# teensy-jst_01_4_v6.net
KiCad netlist of a schematic drawn in EAGLE
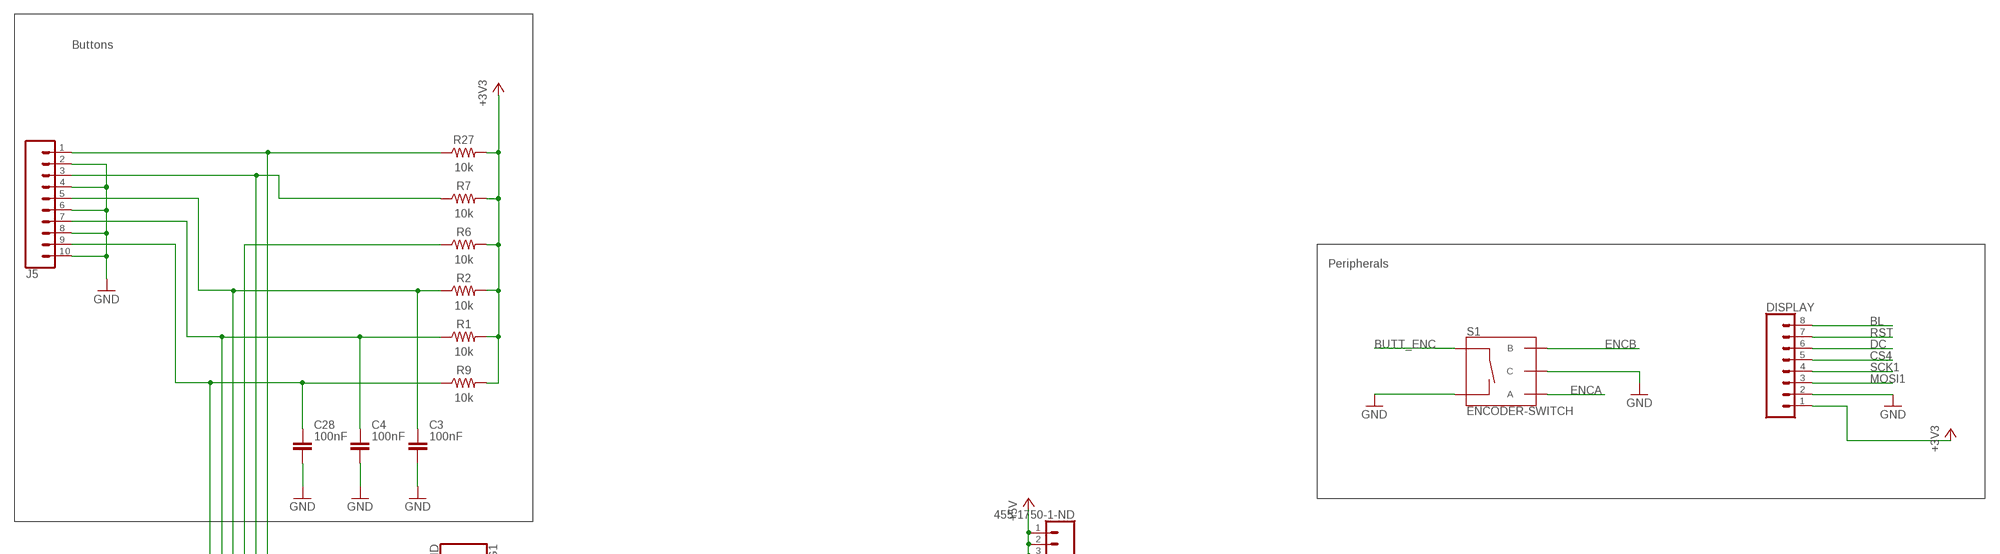
[diagram p0: schematic, sheet 1, part 1 of 3]
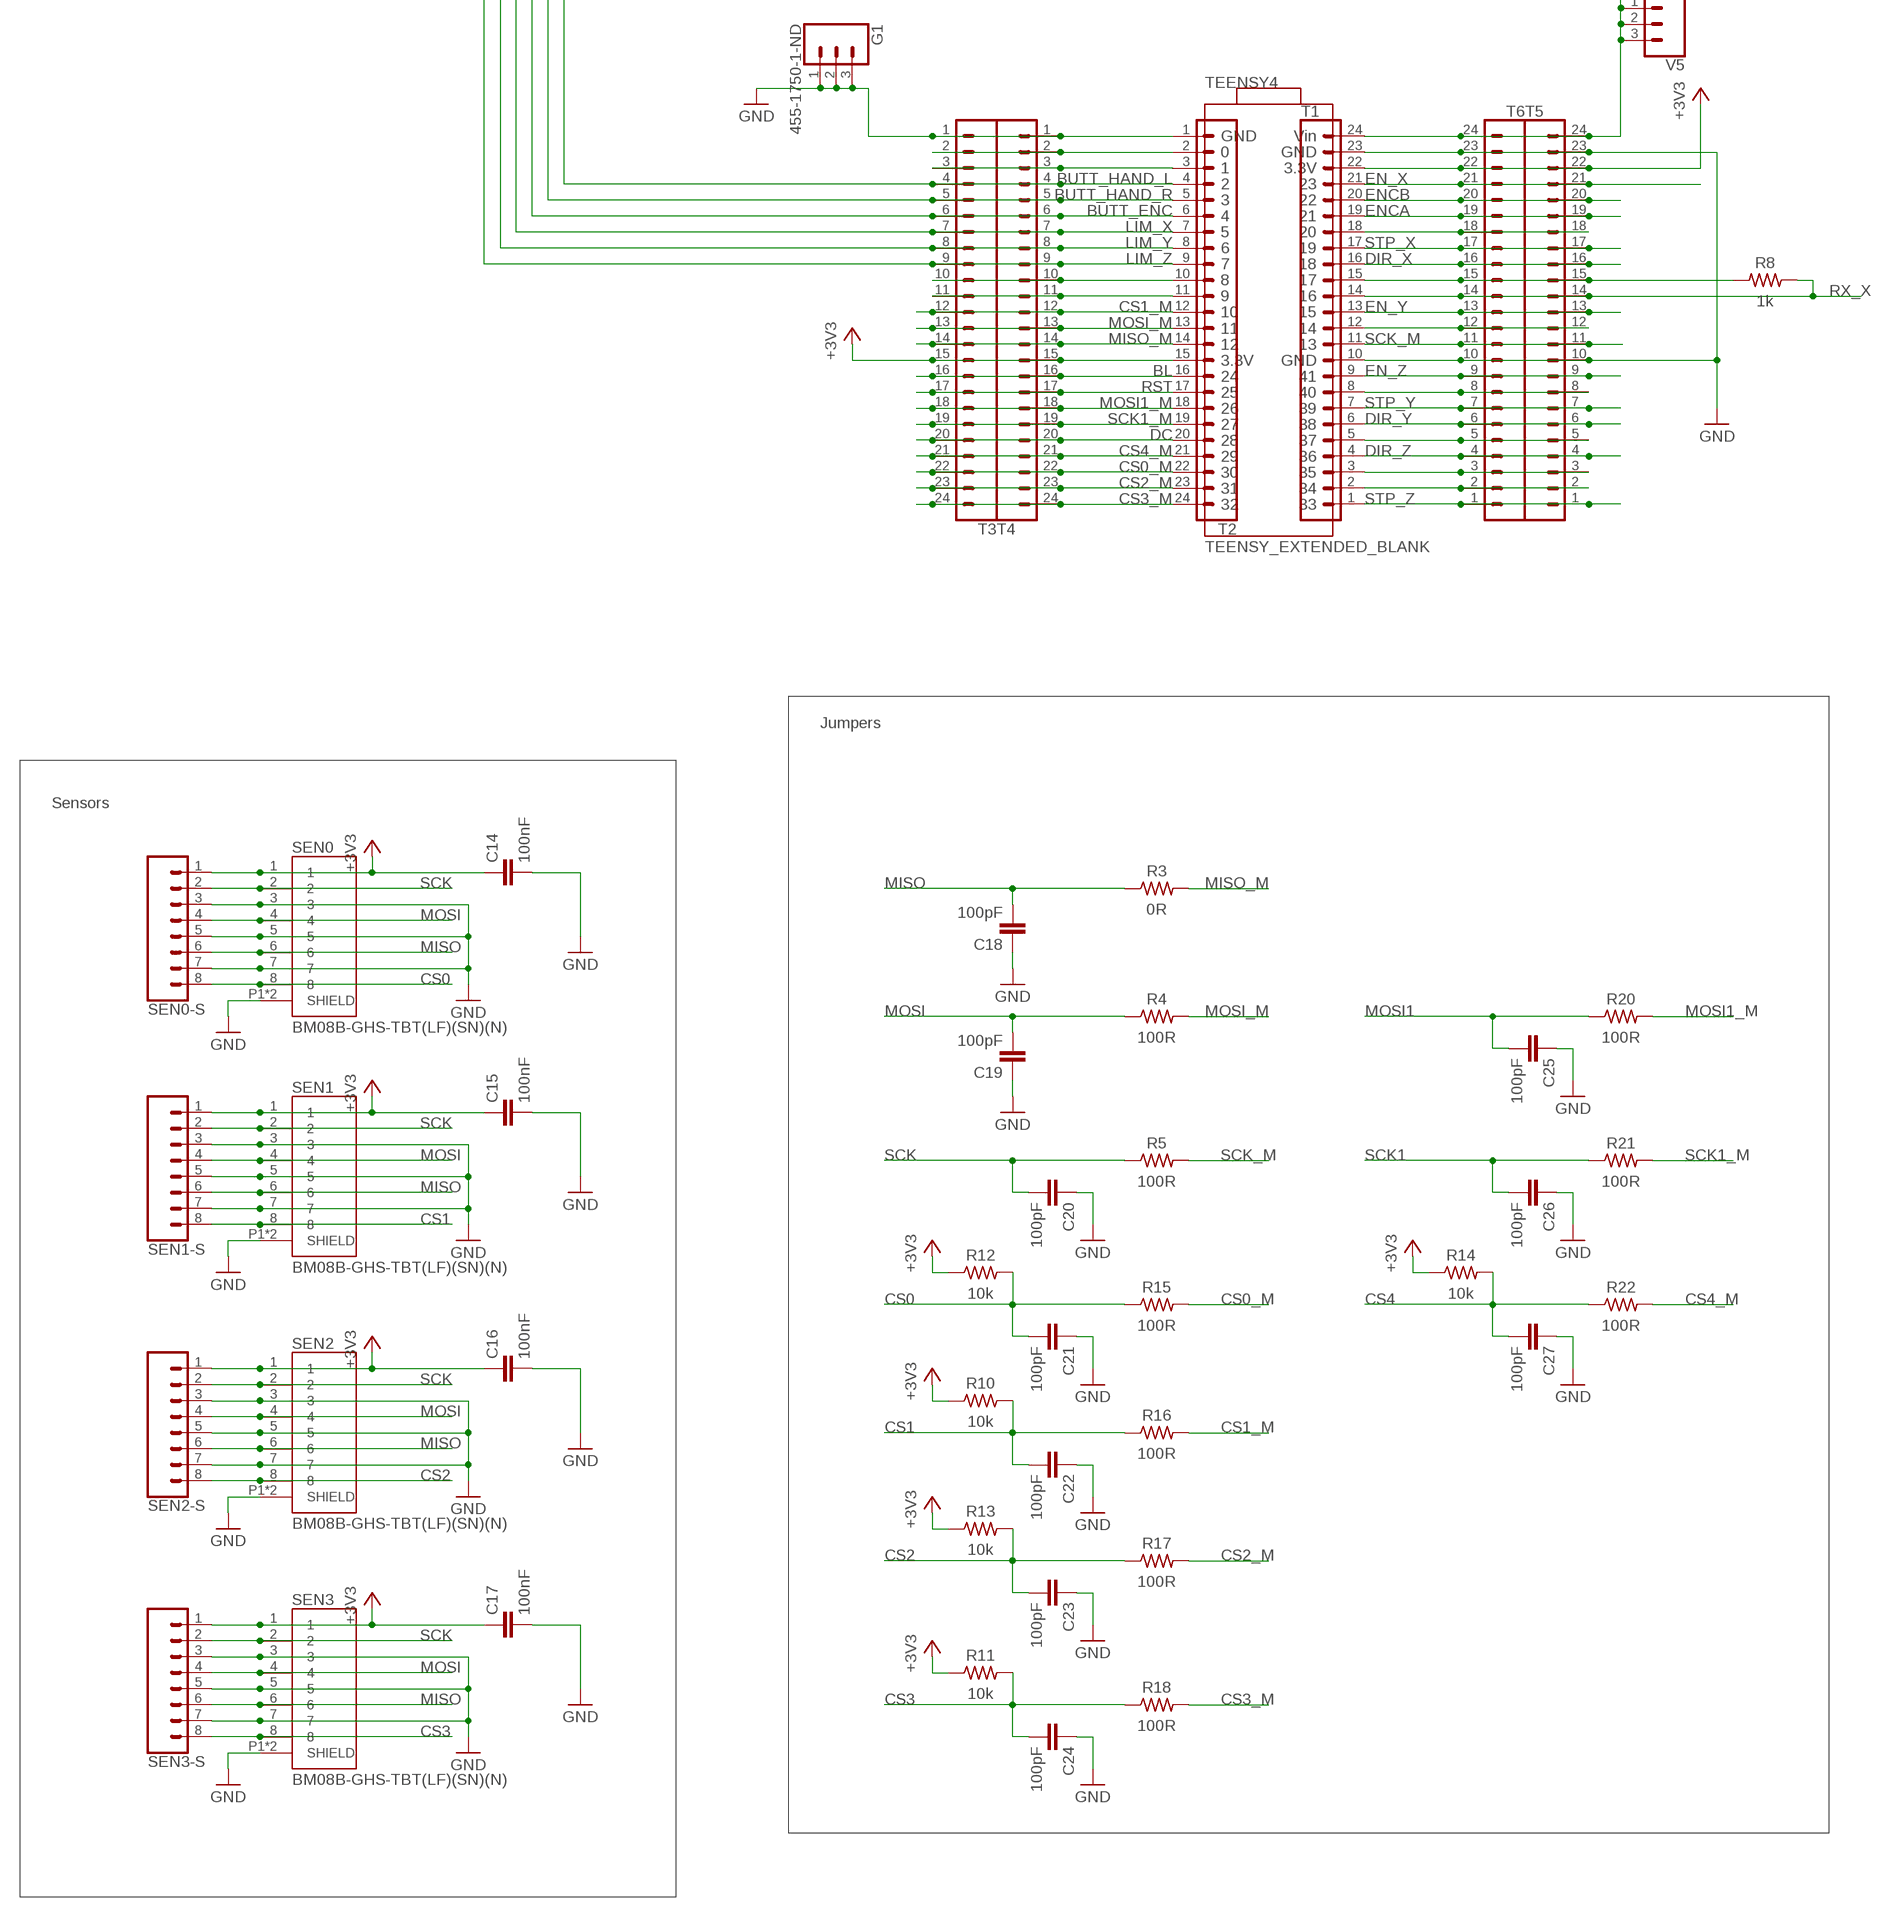
[diagram p1: schematic, sheet 1, part 2 of 3]
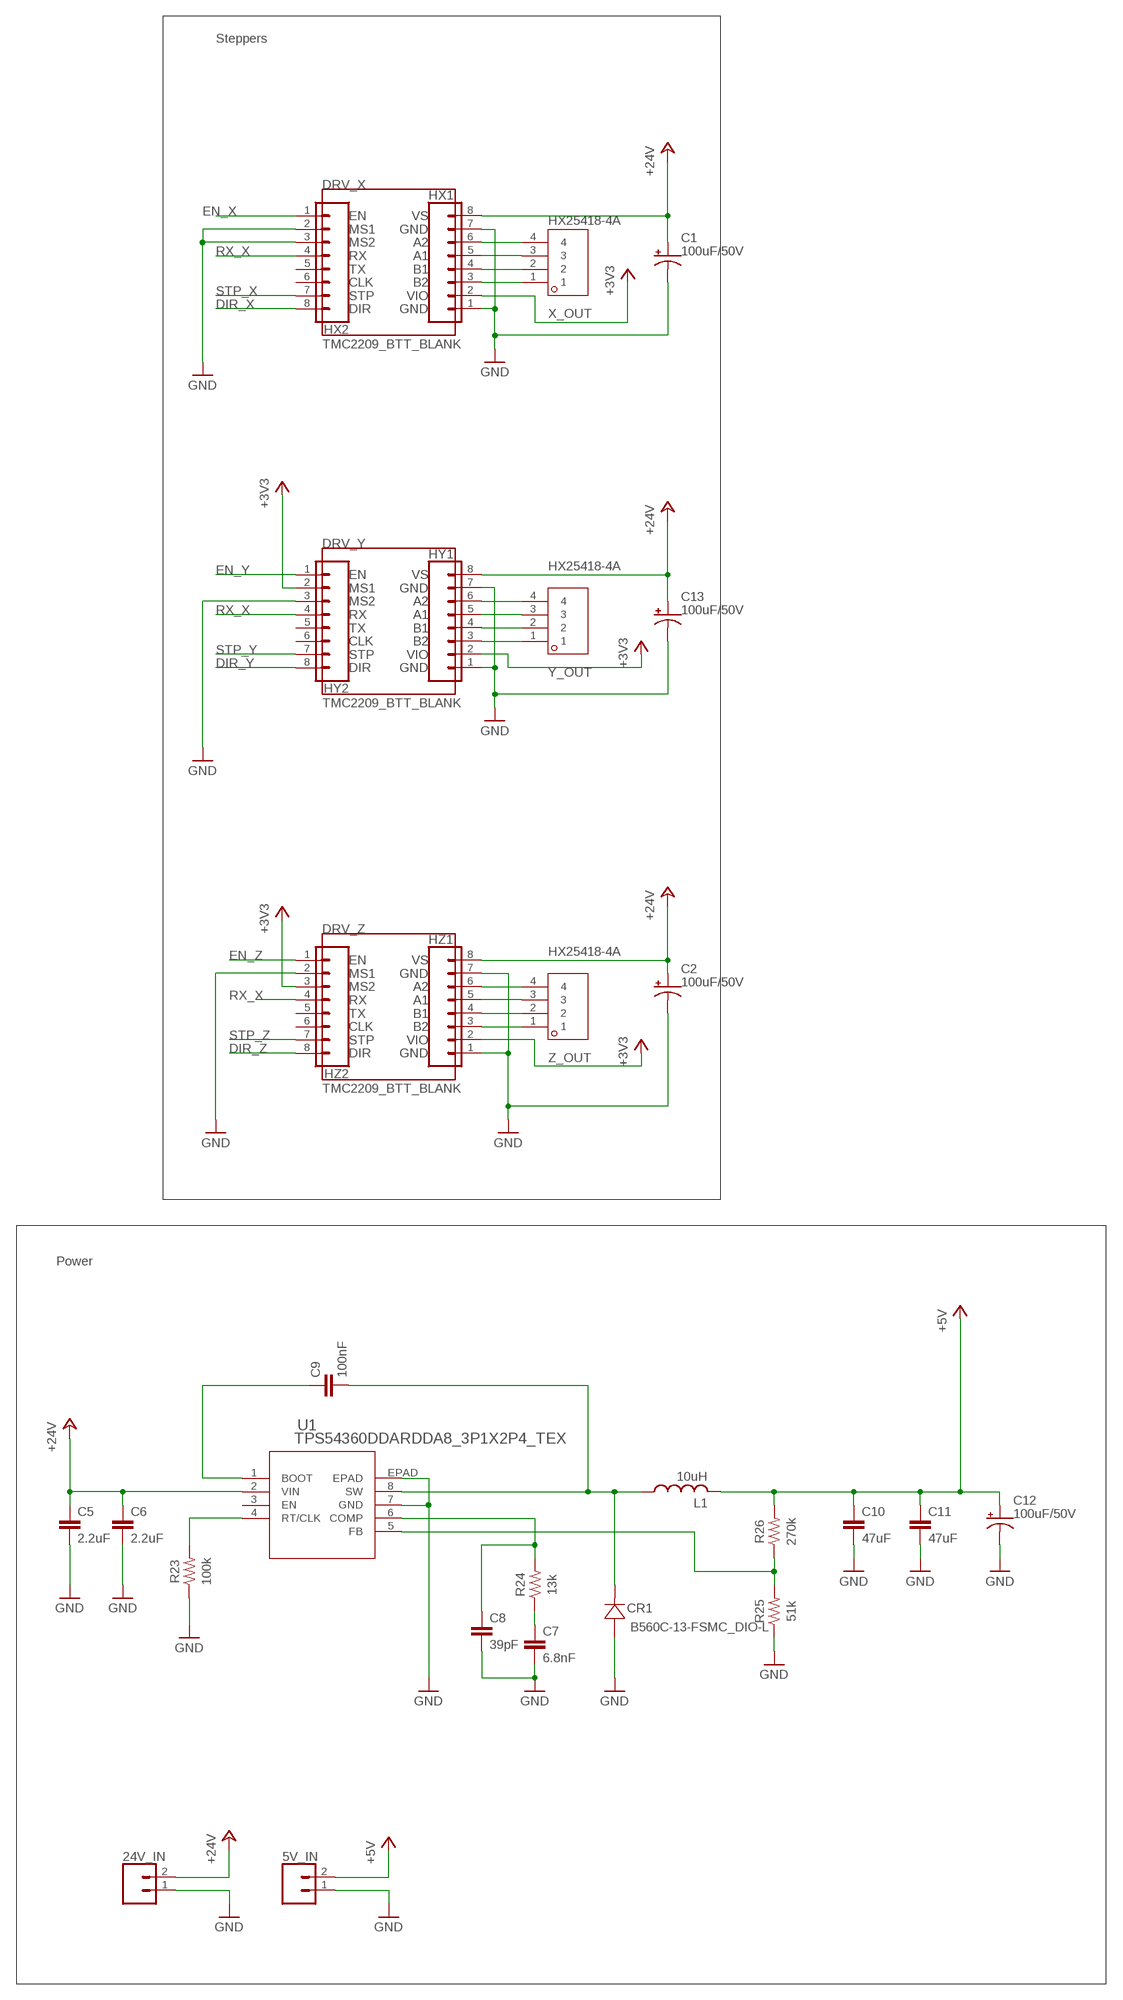
[diagram p2: schematic, sheet 1, part 3 of 3]

(export (version "E")
  (design (tool "Eeschema 10.0.6"))
  (components
    (comp (ref "5V_IN")
      (value "CONN_025MM")
      (footprint "eagle-import:SCREWTERMINAL-5MM-2")
      (libsource (lib "eagle-import") (part "CONN_025MM"))
    )
    (comp (ref "24V_IN")
      (value "CONN_025MM")
      (footprint "eagle-import:SCREWTERMINAL-5MM-2")
      (libsource (lib "eagle-import") (part "CONN_025MM"))
    )
    (comp (ref "C1")
      (value "100uF/50V")
      (footprint "eagle-import:PANASONIC_D")
      (libsource (lib "eagle-import") (part "CPOL-USD"))
    )
    (comp (ref "C2")
      (value "100uF/50V")
      (footprint "eagle-import:PANASONIC_D")
      (libsource (lib "eagle-import") (part "CPOL-USD"))
    )
    (comp (ref "C3")
      (value "100nF")
      (footprint "eagle-import:CAPC1608X85")
      (libsource (lib "eagle-import") (part "CCHIP-0603(1608-METRIC)_"))
    )
    (comp (ref "C4")
      (value "100nF")
      (footprint "eagle-import:CAPC1608X85")
      (libsource (lib "eagle-import") (part "CCHIP-0603(1608-METRIC)_"))
    )
    (comp (ref "C5")
      (value "2.2uF")
      (footprint "eagle-import:CAPC1608X85")
      (libsource (lib "eagle-import") (part "CCHIP-0603(1608-METRIC)_"))
    )
    (comp (ref "C6")
      (value "2.2uF")
      (footprint "eagle-import:CAPC1608X85")
      (libsource (lib "eagle-import") (part "CCHIP-0603(1608-METRIC)_"))
    )
    (comp (ref "C7")
      (value "6.8nF")
      (footprint "eagle-import:CAPC1608X85")
      (libsource (lib "eagle-import") (part "CCHIP-0603(1608-METRIC)_"))
    )
    (comp (ref "C8")
      (value "39pF")
      (footprint "eagle-import:CAPC1005X60")
      (libsource (lib "eagle-import") (part "CCHIP-0402(1005-METRIC)_"))
    )
    (comp (ref "C9")
      (value "100nF")
      (footprint "eagle-import:CAPC1005X60")
      (libsource (lib "eagle-import") (part "CCHIP-0402(1005-METRIC)_"))
    )
    (comp (ref "C10")
      (value "47uF")
      (footprint "eagle-import:CAPC2012X110")
      (libsource (lib "eagle-import") (part "CCHIP-0805(2012-METRIC)_"))
    )
    (comp (ref "C11")
      (value "47uF")
      (footprint "eagle-import:CAPC2012X110")
      (libsource (lib "eagle-import") (part "CCHIP-0805(2012-METRIC)_"))
    )
    (comp (ref "C12")
      (value "100uF/50V")
      (footprint "eagle-import:PANASONIC_D")
      (libsource (lib "eagle-import") (part "CPOL-USD"))
    )
    (comp (ref "C13")
      (value "100uF/50V")
      (footprint "eagle-import:PANASONIC_D")
      (libsource (lib "eagle-import") (part "CPOL-USD"))
    )
    (comp (ref "C14")
      (value "100nF")
      (footprint "eagle-import:CAPC1005X60")
      (libsource (lib "eagle-import") (part "CCHIP-0402(1005-METRIC)_"))
    )
    (comp (ref "C15")
      (value "100nF")
      (footprint "eagle-import:CAPC1005X60")
      (libsource (lib "eagle-import") (part "CCHIP-0402(1005-METRIC)_"))
    )
    (comp (ref "C16")
      (value "100nF")
      (footprint "eagle-import:CAPC1005X60")
      (libsource (lib "eagle-import") (part "CCHIP-0402(1005-METRIC)_"))
    )
    (comp (ref "C17")
      (value "100nF")
      (footprint "eagle-import:CAPC1005X60")
      (libsource (lib "eagle-import") (part "CCHIP-0402(1005-METRIC)_"))
    )
    (comp (ref "C18")
      (value "100pF")
      (footprint "eagle-import:CAPC1005X60")
      (libsource (lib "eagle-import") (part "CCHIP-0402(1005-METRIC)_"))
    )
    (comp (ref "C19")
      (value "100pF")
      (footprint "eagle-import:CAPC1005X60")
      (libsource (lib "eagle-import") (part "CCHIP-0402(1005-METRIC)_"))
    )
    (comp (ref "C20")
      (value "100pF")
      (footprint "eagle-import:CAPC1005X60")
      (libsource (lib "eagle-import") (part "CCHIP-0402(1005-METRIC)_"))
    )
    (comp (ref "C21")
      (value "100pF")
      (footprint "eagle-import:CAPC1005X60")
      (libsource (lib "eagle-import") (part "CCHIP-0402(1005-METRIC)_"))
    )
    (comp (ref "C22")
      (value "100pF")
      (footprint "eagle-import:CAPC1005X60")
      (libsource (lib "eagle-import") (part "CCHIP-0402(1005-METRIC)_"))
    )
    (comp (ref "C23")
      (value "100pF")
      (footprint "eagle-import:CAPC1005X60")
      (libsource (lib "eagle-import") (part "CCHIP-0402(1005-METRIC)_"))
    )
    (comp (ref "C24")
      (value "100pF")
      (footprint "eagle-import:CAPC1005X60")
      (libsource (lib "eagle-import") (part "CCHIP-0402(1005-METRIC)_"))
    )
    (comp (ref "C25")
      (value "100pF")
      (footprint "eagle-import:CAPC1005X60")
      (libsource (lib "eagle-import") (part "CCHIP-0402(1005-METRIC)_"))
    )
    (comp (ref "C26")
      (value "100pF")
      (footprint "eagle-import:CAPC1005X60")
      (libsource (lib "eagle-import") (part "CCHIP-0402(1005-METRIC)_"))
    )
    (comp (ref "C27")
      (value "100pF")
      (footprint "eagle-import:CAPC1005X60")
      (libsource (lib "eagle-import") (part "CCHIP-0402(1005-METRIC)_"))
    )
    (comp (ref "C28")
      (value "100nF")
      (footprint "eagle-import:CAPC1608X85")
      (libsource (lib "eagle-import") (part "CCHIP-0603(1608-METRIC)_"))
    )
    (comp (ref "CR1")
      (value "B560C-13-FSMC_DIO-L")
      (footprint "eagle-import:SMC_DIO-L")
      (fields
        (field (name "MANUFACTURER_PART_NUMBER") "B560C-13-F")
        (field (name "COPYRIGHT") "Copyright (C) 2024 Ultra Librarian. All rights reserved.")
      )
      (libsource (lib "eagle-import") (part "B560C-13-FSMC_DIO-L"))
    )
    (comp (ref "DISPLAY")
      (value "CONN_08\"")
      (footprint "eagle-import:1X08")
      (libsource (lib "eagle-import") (part "CONN_08{dblquote}"))
    )
    (comp (ref "DRV_X")
      (value "TMC2209_BTT_BLANK")
      (footprint "eagle-import:MODULE_TMC2209_BTT_BLANK")
      (libsource (lib "eagle-import") (part "TMC2209_BTT_BLANK"))
    )
    (comp (ref "DRV_Y")
      (value "TMC2209_BTT_BLANK")
      (footprint "eagle-import:MODULE_TMC2209_BTT_BLANK")
      (libsource (lib "eagle-import") (part "TMC2209_BTT_BLANK"))
    )
    (comp (ref "DRV_Z")
      (value "TMC2209_BTT_BLANK")
      (footprint "eagle-import:MODULE_TMC2209_BTT_BLANK")
      (libsource (lib "eagle-import") (part "TMC2209_BTT_BLANK"))
    )
    (comp (ref "G1")
      (value "455-1750-1-ND")
      (footprint "eagle-import:1X03")
      (libsource (lib "eagle-import") (part "CONN_03"))
    )
    (comp (ref "HX1")
      (value "CONN_08\"")
      (footprint "eagle-import:1X08")
      (libsource (lib "eagle-import") (part "CONN_08{dblquote}"))
    )
    (comp (ref "HX2")
      (value "CONN_08\"")
      (footprint "eagle-import:1X08")
      (libsource (lib "eagle-import") (part "CONN_08{dblquote}"))
    )
    (comp (ref "HY1")
      (value "CONN_08\"")
      (footprint "eagle-import:1X08")
      (libsource (lib "eagle-import") (part "CONN_08{dblquote}"))
    )
    (comp (ref "HY2")
      (value "CONN_08\"")
      (footprint "eagle-import:1X08")
      (libsource (lib "eagle-import") (part "CONN_08{dblquote}"))
    )
    (comp (ref "HZ1")
      (value "CONN_08\"")
      (footprint "eagle-import:1X08")
      (libsource (lib "eagle-import") (part "CONN_08{dblquote}"))
    )
    (comp (ref "HZ2")
      (value "CONN_08\"")
      (footprint "eagle-import:1X08")
      (libsource (lib "eagle-import") (part "CONN_08{dblquote}"))
    )
    (comp (ref "J5")
      (value "CONN_10\"")
      (footprint "eagle-import:1X10")
      (libsource (lib "eagle-import") (part "CONN_10{dblquote}"))
    )
    (comp (ref "L1")
      (value "10uH")
      (footprint "eagle-import:MWSA0503S-100MT")
      (libsource (lib "eagle-import") (part "L-USMWSA0503S-100MT"))
    )
    (comp (ref "R1")
      (value "10k")
      (footprint "eagle-import:RESC1608X60")
      (libsource (lib "eagle-import") (part "R-USCHIP-0603(1608-METRIC)_"))
    )
    (comp (ref "R2")
      (value "10k")
      (footprint "eagle-import:RESC1608X60")
      (libsource (lib "eagle-import") (part "R-USCHIP-0603(1608-METRIC)_"))
    )
    (comp (ref "R3")
      (value "0R")
      (footprint "eagle-import:RESC1608X60")
      (libsource (lib "eagle-import") (part "R-USCHIP-0603(1608-METRIC)_"))
    )
    (comp (ref "R4")
      (value "100R")
      (footprint "eagle-import:RESC1608X60")
      (libsource (lib "eagle-import") (part "R-USCHIP-0603(1608-METRIC)_"))
    )
    (comp (ref "R5")
      (value "100R")
      (footprint "eagle-import:RESC1608X60")
      (libsource (lib "eagle-import") (part "R-USCHIP-0603(1608-METRIC)_"))
    )
    (comp (ref "R6")
      (value "10k")
      (footprint "eagle-import:RESC1608X60")
      (libsource (lib "eagle-import") (part "R-USCHIP-0603(1608-METRIC)_"))
    )
    (comp (ref "R7")
      (value "10k")
      (footprint "eagle-import:RESC1608X60")
      (libsource (lib "eagle-import") (part "R-USCHIP-0603(1608-METRIC)_"))
    )
    (comp (ref "R8")
      (value "1k")
      (footprint "eagle-import:RESC1608X60")
      (libsource (lib "eagle-import") (part "R-USCHIP-0603(1608-METRIC)_"))
    )
    (comp (ref "R9")
      (value "10k")
      (footprint "eagle-import:RESC1608X60")
      (libsource (lib "eagle-import") (part "R-USCHIP-0603(1608-METRIC)_"))
    )
    (comp (ref "R10")
      (value "10k")
      (footprint "eagle-import:RESC1608X60")
      (libsource (lib "eagle-import") (part "R-USCHIP-0603(1608-METRIC)_"))
    )
    (comp (ref "R11")
      (value "10k")
      (footprint "eagle-import:RESC1608X60")
      (libsource (lib "eagle-import") (part "R-USCHIP-0603(1608-METRIC)_"))
    )
    (comp (ref "R12")
      (value "10k")
      (footprint "eagle-import:RESC1608X60")
      (libsource (lib "eagle-import") (part "R-USCHIP-0603(1608-METRIC)_"))
    )
    (comp (ref "R13")
      (value "10k")
      (footprint "eagle-import:RESC1608X60")
      (libsource (lib "eagle-import") (part "R-USCHIP-0603(1608-METRIC)_"))
    )
    (comp (ref "R14")
      (value "10k")
      (footprint "eagle-import:RESC1608X60")
      (libsource (lib "eagle-import") (part "R-USCHIP-0603(1608-METRIC)_"))
    )
    (comp (ref "R15")
      (value "100R")
      (footprint "eagle-import:RESC1608X60")
      (libsource (lib "eagle-import") (part "R-USCHIP-0603(1608-METRIC)_"))
    )
    (comp (ref "R16")
      (value "100R")
      (footprint "eagle-import:RESC1608X60")
      (libsource (lib "eagle-import") (part "R-USCHIP-0603(1608-METRIC)_"))
    )
    (comp (ref "R17")
      (value "100R")
      (footprint "eagle-import:RESC1608X60")
      (libsource (lib "eagle-import") (part "R-USCHIP-0603(1608-METRIC)_"))
    )
    (comp (ref "R18")
      (value "100R")
      (footprint "eagle-import:RESC1608X60")
      (libsource (lib "eagle-import") (part "R-USCHIP-0603(1608-METRIC)_"))
    )
    (comp (ref "R20")
      (value "100R")
      (footprint "eagle-import:RESC1608X60")
      (libsource (lib "eagle-import") (part "R-USCHIP-0603(1608-METRIC)_"))
    )
    (comp (ref "R21")
      (value "100R")
      (footprint "eagle-import:RESC1608X60")
      (libsource (lib "eagle-import") (part "R-USCHIP-0603(1608-METRIC)_"))
    )
    (comp (ref "R22")
      (value "100R")
      (footprint "eagle-import:RESC1608X60")
      (libsource (lib "eagle-import") (part "R-USCHIP-0603(1608-METRIC)_"))
    )
    (comp (ref "R23")
      (value "100k")
      (footprint "eagle-import:RESC1005X40")
      (libsource (lib "eagle-import") (part "R-USCHIP-0402(1005-METRIC)_"))
    )
    (comp (ref "R24")
      (value "13k")
      (footprint "eagle-import:RESC1608X60")
      (libsource (lib "eagle-import") (part "R-USCHIP-0603(1608-METRIC)_"))
    )
    (comp (ref "R25")
      (value "51k")
      (footprint "eagle-import:RESC1608X60")
      (libsource (lib "eagle-import") (part "R-USCHIP-0603(1608-METRIC)_"))
    )
    (comp (ref "R26")
      (value "270k")
      (footprint "eagle-import:RESC1005X40")
      (libsource (lib "eagle-import") (part "R-USCHIP-0402(1005-METRIC)_"))
    )
    (comp (ref "R27")
      (value "10k")
      (footprint "eagle-import:RESC1608X60")
      (libsource (lib "eagle-import") (part "R-USCHIP-0603(1608-METRIC)_"))
    )
    (comp (ref "S1")
      (value "ENCODER-SWITCH")
      (footprint "eagle-import:ROTARY_ENC_PLAIN")
      (libsource (lib "eagle-import") (part "ENCODER-SWITCH"))
    )
    (comp (ref "SEN0")
      (value "BM08B-GHS-TBT(LF)(SN)(N)")
      (footprint "eagle-import:JST_BM08B-GHS-TBT(LF)(SN)(N)")
      (fields (field (name "MF") "JST Sales"))
      (libsource (lib "eagle-import") (part "BM08B-GHS-TBT(LF)(SN)(N)"))
    )
    (comp (ref "SEN0-S")
      (value "CONN_08\"")
      (footprint "eagle-import:1X08")
      (libsource (lib "eagle-import") (part "CONN_08{dblquote}"))
    )
    (comp (ref "SEN1")
      (value "BM08B-GHS-TBT(LF)(SN)(N)")
      (footprint "eagle-import:JST_BM08B-GHS-TBT(LF)(SN)(N)")
      (fields (field (name "MF") "JST Sales"))
      (libsource (lib "eagle-import") (part "BM08B-GHS-TBT(LF)(SN)(N)"))
    )
    (comp (ref "SEN1-S")
      (value "CONN_08\"")
      (footprint "eagle-import:1X08")
      (libsource (lib "eagle-import") (part "CONN_08{dblquote}"))
    )
    (comp (ref "SEN2")
      (value "BM08B-GHS-TBT(LF)(SN)(N)")
      (footprint "eagle-import:JST_BM08B-GHS-TBT(LF)(SN)(N)")
      (fields (field (name "MF") "JST Sales"))
      (libsource (lib "eagle-import") (part "BM08B-GHS-TBT(LF)(SN)(N)"))
    )
    (comp (ref "SEN2-S")
      (value "CONN_08\"")
      (footprint "eagle-import:1X08")
      (libsource (lib "eagle-import") (part "CONN_08{dblquote}"))
    )
    (comp (ref "SEN3")
      (value "BM08B-GHS-TBT(LF)(SN)(N)")
      (footprint "eagle-import:JST_BM08B-GHS-TBT(LF)(SN)(N)")
      (fields (field (name "MF") "JST Sales"))
      (libsource (lib "eagle-import") (part "BM08B-GHS-TBT(LF)(SN)(N)"))
    )
    (comp (ref "SEN3-S")
      (value "CONN_08\"")
      (footprint "eagle-import:1X08")
      (libsource (lib "eagle-import") (part "CONN_08{dblquote}"))
    )
    (comp (ref "T1")
      (value "CONN_24")
      (footprint "eagle-import:1X24")
      (libsource (lib "eagle-import") (part "CONN_24"))
    )
    (comp (ref "T2")
      (value "CONN_24")
      (footprint "eagle-import:1X24")
      (libsource (lib "eagle-import") (part "CONN_24"))
    )
    (comp (ref "T3")
      (value "CONN_24")
      (footprint "eagle-import:1X24")
      (libsource (lib "eagle-import") (part "CONN_24"))
    )
    (comp (ref "T4")
      (value "CONN_24")
      (footprint "eagle-import:1X24")
      (libsource (lib "eagle-import") (part "CONN_24"))
    )
    (comp (ref "T5")
      (value "CONN_24")
      (footprint "eagle-import:1X24")
      (libsource (lib "eagle-import") (part "CONN_24"))
    )
    (comp (ref "T6")
      (value "CONN_24")
      (footprint "eagle-import:1X24")
      (libsource (lib "eagle-import") (part "CONN_24"))
    )
    (comp (ref "TEENSY4")
      (value "TEENSY_EXTENDED_BLANK")
      (footprint "eagle-import:TEENSY_EXTENDED_BLANK")
      (libsource (lib "eagle-import") (part "TEENSY_EXTENDED_BLANK"))
    )
    (comp (ref "U1")
      (value "TPS54360DDARDDA8_3P1X2P4_TEX")
      (footprint "eagle-import:DDA8_3P1X2P4_TEX")
      (fields
        (field (name "MANUFACTURER_PART_NUMBER") "TPS54360DDAR")
        (field (name "COPYRIGHT") "Copyright (C) 2024 Ultra Librarian. All rights reserved.")
      )
      (libsource (lib "eagle-import") (part "TPS54360DDARDDA8_3P1X2P4_TEX"))
    )
    (comp (ref "V5")
      (value "455-1750-1-ND")
      (footprint "eagle-import:1X03")
      (libsource (lib "eagle-import") (part "CONN_03"))
    )
    (comp (ref "X_OUT")
      (value "HX25418-4A")
      (footprint "eagle-import:HX25418-4A")
      (libsource (lib "eagle-import") (part "HX25418-4A"))
    )
    (comp (ref "Y_OUT")
      (value "HX25418-4A")
      (footprint "eagle-import:HX25418-4A")
      (libsource (lib "eagle-import") (part "HX25418-4A"))
    )
    (comp (ref "Z_OUT")
      (value "HX25418-4A")
      (footprint "eagle-import:HX25418-4A")
      (libsource (lib "eagle-import") (part "HX25418-4A"))
    )
  )
  (nets
    (net (code "1") (name "+3V3") (class "Default")
      (node (ref "C14") (pin "1") (pinfunction "1_1") (pintype "passive"))
      (node (ref "C15") (pin "1") (pinfunction "1_1") (pintype "passive"))
      (node (ref "C16") (pin "1") (pinfunction "1_1") (pintype "passive"))
      (node (ref "C17") (pin "1") (pinfunction "1_1") (pintype "passive"))
      (node (ref "DISPLAY") (pin "1") (pinfunction "1_1") (pintype "passive"))
      (node (ref "HX1") (pin "2") (pinfunction "2_2") (pintype "passive"))
      (node (ref "HY1") (pin "2") (pinfunction "2_2") (pintype "passive"))
      (node (ref "HY2") (pin "2") (pinfunction "2_2") (pintype "passive"))
      (node (ref "HZ1") (pin "2") (pinfunction "2_2") (pintype "passive"))
      (node (ref "HZ2") (pin "3") (pinfunction "3_3") (pintype "passive"))
      (node (ref "R1") (pin "2") (pinfunction "2_2") (pintype "passive"))
      (node (ref "R10") (pin "1") (pinfunction "1_1") (pintype "passive"))
      (node (ref "R11") (pin "1") (pinfunction "1_1") (pintype "passive"))
      (node (ref "R12") (pin "1") (pinfunction "1_1") (pintype "passive"))
      (node (ref "R13") (pin "1") (pinfunction "1_1") (pintype "passive"))
      (node (ref "R14") (pin "1") (pinfunction "1_1") (pintype "passive"))
      (node (ref "R2") (pin "2") (pinfunction "2_2") (pintype "passive"))
      (node (ref "R27") (pin "2") (pinfunction "2_2") (pintype "passive"))
      (node (ref "R6") (pin "2") (pinfunction "2_2") (pintype "passive"))
      (node (ref "R7") (pin "2") (pinfunction "2_2") (pintype "passive"))
      (node (ref "R9") (pin "2") (pinfunction "2_2") (pintype "passive"))
      (node (ref "SEN0") (pin "1") (pinfunction "1_1") (pintype "passive"))
      (node (ref "SEN0-S") (pin "1") (pinfunction "1_1") (pintype "passive"))
      (node (ref "SEN1") (pin "1") (pinfunction "1_1") (pintype "passive"))
      (node (ref "SEN1-S") (pin "1") (pinfunction "1_1") (pintype "passive"))
      (node (ref "SEN2") (pin "1") (pinfunction "1_1") (pintype "passive"))
      (node (ref "SEN2-S") (pin "1") (pinfunction "1_1") (pintype "passive"))
      (node (ref "SEN3") (pin "1") (pinfunction "1_1") (pintype "passive"))
      (node (ref "SEN3-S") (pin "1") (pinfunction "1_1") (pintype "passive"))
      (node (ref "T1") (pin "22") (pinfunction "22_22") (pintype "passive"))
      (node (ref "T2") (pin "15") (pinfunction "15_15") (pintype "passive"))
      (node (ref "T3") (pin "15") (pinfunction "15_15") (pintype "passive"))
      (node (ref "T4") (pin "15") (pinfunction "15_15") (pintype "passive"))
      (node (ref "T5") (pin "22") (pinfunction "22_22") (pintype "passive"))
      (node (ref "T6") (pin "22") (pinfunction "22_22") (pintype "passive"))
    )
    (net (code "2") (name "+5V") (class "Default")
      (node (ref "5V_IN") (pin "2") (pinfunction "2_2") (pintype "passive"))
      (node (ref "C10") (pin "1") (pinfunction "1_1") (pintype "passive"))
      (node (ref "C11") (pin "1") (pinfunction "1_1") (pintype "passive"))
      (node (ref "C12") (pin "+") (pinfunction "+_+") (pintype "passive"))
      (node (ref "L1") (pin "2") (pinfunction "2_2") (pintype "passive"))
      (node (ref "R26") (pin "2") (pinfunction "2_2") (pintype "passive"))
      (node (ref "T1") (pin "24") (pinfunction "24_24") (pintype "passive"))
      (node (ref "T5") (pin "24") (pinfunction "24_24") (pintype "passive"))
      (node (ref "T6") (pin "24") (pinfunction "24_24") (pintype "passive"))
      (node (ref "V5") (pin "1") (pinfunction "1_1") (pintype "passive"))
      (node (ref "V5") (pin "2") (pinfunction "2_2") (pintype "passive"))
      (node (ref "V5") (pin "3") (pinfunction "3_3") (pintype "passive"))
    )
    (net (code "3") (name "+24V") (class "Default")
      (node (ref "24V_IN") (pin "2") (pinfunction "2_2") (pintype "passive"))
      (node (ref "C1") (pin "+") (pinfunction "+_+") (pintype "passive"))
      (node (ref "C13") (pin "+") (pinfunction "+_+") (pintype "passive"))
      (node (ref "C2") (pin "+") (pinfunction "+_+") (pintype "passive"))
      (node (ref "C5") (pin "1") (pinfunction "1_1") (pintype "passive"))
      (node (ref "C6") (pin "1") (pinfunction "1_1") (pintype "passive"))
      (node (ref "HX1") (pin "8") (pinfunction "8_8") (pintype "passive"))
      (node (ref "HY1") (pin "8") (pinfunction "8_8") (pintype "passive"))
      (node (ref "HZ1") (pin "8") (pinfunction "8_8") (pintype "passive"))
      (node (ref "U1") (pin "2") (pinfunction "VIN_2") (pintype "input"))
    )
    (net (code "4") (name "/BL") (class "Default")
      (node (ref "DISPLAY") (pin "8") (pinfunction "8_8") (pintype "passive"))
      (node (ref "T2") (pin "16") (pinfunction "16_16") (pintype "passive"))
      (node (ref "T3") (pin "16") (pinfunction "16_16") (pintype "passive"))
      (node (ref "T4") (pin "16") (pinfunction "16_16") (pintype "passive"))
    )
    (net (code "5") (name "/BUTT_ENC") (class "Default")
      (node (ref "R6") (pin "1") (pinfunction "1_1") (pintype "passive"))
      (node (ref "S1") (pin "SW+") (pinfunction "SW+_SW+") (pintype "bidirectional"))
      (node (ref "T2") (pin "6") (pinfunction "6_6") (pintype "passive"))
      (node (ref "T3") (pin "6") (pinfunction "6_6") (pintype "passive"))
      (node (ref "T4") (pin "6") (pinfunction "6_6") (pintype "passive"))
    )
    (net (code "6") (name "/BUTT_HAND_L") (class "Default")
      (node (ref "J5") (pin "1") (pinfunction "1_1") (pintype "passive"))
      (node (ref "R27") (pin "1") (pinfunction "1_1") (pintype "passive"))
      (node (ref "T2") (pin "4") (pinfunction "4_4") (pintype "passive"))
      (node (ref "T3") (pin "4") (pinfunction "4_4") (pintype "passive"))
      (node (ref "T4") (pin "4") (pinfunction "4_4") (pintype "passive"))
    )
    (net (code "7") (name "/BUTT_HAND_R") (class "Default")
      (node (ref "J5") (pin "3") (pinfunction "3_3") (pintype "passive"))
      (node (ref "R7") (pin "1") (pinfunction "1_1") (pintype "passive"))
      (node (ref "T2") (pin "5") (pinfunction "5_5") (pintype "passive"))
      (node (ref "T3") (pin "5") (pinfunction "5_5") (pintype "passive"))
      (node (ref "T4") (pin "5") (pinfunction "5_5") (pintype "passive"))
    )
    (net (code "8") (name "/CS0") (class "Default")
      (node (ref "C21") (pin "2") (pinfunction "2_2") (pintype "passive"))
      (node (ref "R12") (pin "2") (pinfunction "2_2") (pintype "passive"))
      (node (ref "R15") (pin "1") (pinfunction "1_1") (pintype "passive"))
      (node (ref "SEN0") (pin "8") (pinfunction "8_8") (pintype "passive"))
      (node (ref "SEN0-S") (pin "8") (pinfunction "8_8") (pintype "passive"))
    )
    (net (code "9") (name "/CS0_M") (class "Default")
      (node (ref "R15") (pin "2") (pinfunction "2_2") (pintype "passive"))
      (node (ref "T2") (pin "22") (pinfunction "22_22") (pintype "passive"))
      (node (ref "T3") (pin "22") (pinfunction "22_22") (pintype "passive"))
      (node (ref "T4") (pin "22") (pinfunction "22_22") (pintype "passive"))
    )
    (net (code "10") (name "/CS1") (class "Default")
      (node (ref "C22") (pin "2") (pinfunction "2_2") (pintype "passive"))
      (node (ref "R10") (pin "2") (pinfunction "2_2") (pintype "passive"))
      (node (ref "R16") (pin "1") (pinfunction "1_1") (pintype "passive"))
      (node (ref "SEN1") (pin "8") (pinfunction "8_8") (pintype "passive"))
      (node (ref "SEN1-S") (pin "8") (pinfunction "8_8") (pintype "passive"))
    )
    (net (code "11") (name "/CS1_M") (class "Default")
      (node (ref "R16") (pin "2") (pinfunction "2_2") (pintype "passive"))
      (node (ref "T2") (pin "12") (pinfunction "12_12") (pintype "passive"))
      (node (ref "T3") (pin "12") (pinfunction "12_12") (pintype "passive"))
      (node (ref "T4") (pin "12") (pinfunction "12_12") (pintype "passive"))
    )
    (net (code "12") (name "/CS2") (class "Default")
      (node (ref "C23") (pin "2") (pinfunction "2_2") (pintype "passive"))
      (node (ref "R13") (pin "2") (pinfunction "2_2") (pintype "passive"))
      (node (ref "R17") (pin "1") (pinfunction "1_1") (pintype "passive"))
      (node (ref "SEN2") (pin "8") (pinfunction "8_8") (pintype "passive"))
      (node (ref "SEN2-S") (pin "8") (pinfunction "8_8") (pintype "passive"))
    )
    (net (code "13") (name "/CS2_M") (class "Default")
      (node (ref "R17") (pin "2") (pinfunction "2_2") (pintype "passive"))
      (node (ref "T2") (pin "23") (pinfunction "23_23") (pintype "passive"))
      (node (ref "T3") (pin "23") (pinfunction "23_23") (pintype "passive"))
      (node (ref "T4") (pin "23") (pinfunction "23_23") (pintype "passive"))
    )
    (net (code "14") (name "/CS3") (class "Default")
      (node (ref "C24") (pin "2") (pinfunction "2_2") (pintype "passive"))
      (node (ref "R11") (pin "2") (pinfunction "2_2") (pintype "passive"))
      (node (ref "R18") (pin "1") (pinfunction "1_1") (pintype "passive"))
      (node (ref "SEN3") (pin "8") (pinfunction "8_8") (pintype "passive"))
      (node (ref "SEN3-S") (pin "8") (pinfunction "8_8") (pintype "passive"))
    )
    (net (code "15") (name "/CS3_M") (class "Default")
      (node (ref "R18") (pin "2") (pinfunction "2_2") (pintype "passive"))
      (node (ref "T2") (pin "24") (pinfunction "24_24") (pintype "passive"))
      (node (ref "T3") (pin "24") (pinfunction "24_24") (pintype "passive"))
      (node (ref "T4") (pin "24") (pinfunction "24_24") (pintype "passive"))
    )
    (net (code "16") (name "/CS4") (class "Default")
      (node (ref "C27") (pin "2") (pinfunction "2_2") (pintype "passive"))
      (node (ref "DISPLAY") (pin "5") (pinfunction "5_5") (pintype "passive"))
      (node (ref "R14") (pin "2") (pinfunction "2_2") (pintype "passive"))
      (node (ref "R22") (pin "1") (pinfunction "1_1") (pintype "passive"))
    )
    (net (code "17") (name "/CS4_M") (class "Default")
      (node (ref "R22") (pin "2") (pinfunction "2_2") (pintype "passive"))
      (node (ref "T2") (pin "21") (pinfunction "21_21") (pintype "passive"))
      (node (ref "T3") (pin "21") (pinfunction "21_21") (pintype "passive"))
      (node (ref "T4") (pin "21") (pinfunction "21_21") (pintype "passive"))
    )
    (net (code "18") (name "/DC") (class "Default")
      (node (ref "DISPLAY") (pin "6") (pinfunction "6_6") (pintype "passive"))
      (node (ref "T2") (pin "20") (pinfunction "20_20") (pintype "passive"))
      (node (ref "T3") (pin "20") (pinfunction "20_20") (pintype "passive"))
      (node (ref "T4") (pin "20") (pinfunction "20_20") (pintype "passive"))
    )
    (net (code "19") (name "/DIR_X") (class "Default")
      (node (ref "HX2") (pin "8") (pinfunction "8_8") (pintype "passive"))
      (node (ref "T1") (pin "16") (pinfunction "16_16") (pintype "passive"))
      (node (ref "T5") (pin "16") (pinfunction "16_16") (pintype "passive"))
      (node (ref "T6") (pin "16") (pinfunction "16_16") (pintype "passive"))
    )
    (net (code "20") (name "/DIR_Y") (class "Default")
      (node (ref "HY2") (pin "8") (pinfunction "8_8") (pintype "passive"))
      (node (ref "T1") (pin "6") (pinfunction "6_6") (pintype "passive"))
      (node (ref "T5") (pin "6") (pinfunction "6_6") (pintype "passive"))
      (node (ref "T6") (pin "6") (pinfunction "6_6") (pintype "passive"))
    )
    (net (code "21") (name "/DIR_Z") (class "Default")
      (node (ref "HZ2") (pin "8") (pinfunction "8_8") (pintype "passive"))
      (node (ref "T1") (pin "4") (pinfunction "4_4") (pintype "passive"))
      (node (ref "T5") (pin "4") (pinfunction "4_4") (pintype "passive"))
      (node (ref "T6") (pin "4") (pinfunction "4_4") (pintype "passive"))
    )
    (net (code "22") (name "/ENCA") (class "Default")
      (node (ref "S1") (pin "A") (pinfunction "A_A") (pintype "bidirectional"))
      (node (ref "T1") (pin "19") (pinfunction "19_19") (pintype "passive"))
      (node (ref "T5") (pin "19") (pinfunction "19_19") (pintype "passive"))
      (node (ref "T6") (pin "19") (pinfunction "19_19") (pintype "passive"))
    )
    (net (code "23") (name "/ENCB") (class "Default")
      (node (ref "S1") (pin "B") (pinfunction "B_B") (pintype "bidirectional"))
      (node (ref "T1") (pin "20") (pinfunction "20_20") (pintype "passive"))
      (node (ref "T5") (pin "20") (pinfunction "20_20") (pintype "passive"))
      (node (ref "T6") (pin "20") (pinfunction "20_20") (pintype "passive"))
    )
    (net (code "24") (name "/EN_X") (class "Default")
      (node (ref "HX2") (pin "1") (pinfunction "1_1") (pintype "passive"))
      (node (ref "T1") (pin "21") (pinfunction "21_21") (pintype "passive"))
      (node (ref "T5") (pin "21") (pinfunction "21_21") (pintype "passive"))
      (node (ref "T6") (pin "21") (pinfunction "21_21") (pintype "passive"))
    )
    (net (code "25") (name "/EN_Y") (class "Default")
      (node (ref "HY2") (pin "1") (pinfunction "1_1") (pintype "passive"))
      (node (ref "T1") (pin "13") (pinfunction "13_13") (pintype "passive"))
      (node (ref "T5") (pin "13") (pinfunction "13_13") (pintype "passive"))
      (node (ref "T6") (pin "13") (pinfunction "13_13") (pintype "passive"))
    )
    (net (code "26") (name "/EN_Z") (class "Default")
      (node (ref "HZ2") (pin "1") (pinfunction "1_1") (pintype "passive"))
      (node (ref "T1") (pin "9") (pinfunction "9_9") (pintype "passive"))
      (node (ref "T5") (pin "9") (pinfunction "9_9") (pintype "passive"))
      (node (ref "T6") (pin "9") (pinfunction "9_9") (pintype "passive"))
    )
    (net (code "27") (name "/LIM_X") (class "Default")
      (node (ref "C3") (pin "1") (pinfunction "1_1") (pintype "passive"))
      (node (ref "J5") (pin "5") (pinfunction "5_5") (pintype "passive"))
      (node (ref "R2") (pin "1") (pinfunction "1_1") (pintype "passive"))
      (node (ref "T2") (pin "7") (pinfunction "7_7") (pintype "passive"))
      (node (ref "T3") (pin "7") (pinfunction "7_7") (pintype "passive"))
      (node (ref "T4") (pin "7") (pinfunction "7_7") (pintype "passive"))
    )
    (net (code "28") (name "/LIM_Y") (class "Default")
      (node (ref "C4") (pin "1") (pinfunction "1_1") (pintype "passive"))
      (node (ref "J5") (pin "7") (pinfunction "7_7") (pintype "passive"))
      (node (ref "R1") (pin "1") (pinfunction "1_1") (pintype "passive"))
      (node (ref "T2") (pin "8") (pinfunction "8_8") (pintype "passive"))
      (node (ref "T3") (pin "8") (pinfunction "8_8") (pintype "passive"))
      (node (ref "T4") (pin "8") (pinfunction "8_8") (pintype "passive"))
    )
    (net (code "29") (name "/LIM_Z") (class "Default")
      (node (ref "C28") (pin "1") (pinfunction "1_1") (pintype "passive"))
      (node (ref "J5") (pin "9") (pinfunction "9_9") (pintype "passive"))
      (node (ref "R9") (pin "1") (pinfunction "1_1") (pintype "passive"))
      (node (ref "T2") (pin "9") (pinfunction "9_9") (pintype "passive"))
      (node (ref "T3") (pin "9") (pinfunction "9_9") (pintype "passive"))
      (node (ref "T4") (pin "9") (pinfunction "9_9") (pintype "passive"))
    )
    (net (code "30") (name "/MISO") (class "Default")
      (node (ref "C18") (pin "2") (pinfunction "2_2") (pintype "passive"))
      (node (ref "R3") (pin "1") (pinfunction "1_1") (pintype "passive"))
      (node (ref "SEN0") (pin "6") (pinfunction "6_6") (pintype "passive"))
      (node (ref "SEN0-S") (pin "6") (pinfunction "6_6") (pintype "passive"))
      (node (ref "SEN1") (pin "6") (pinfunction "6_6") (pintype "passive"))
      (node (ref "SEN1-S") (pin "6") (pinfunction "6_6") (pintype "passive"))
      (node (ref "SEN2") (pin "6") (pinfunction "6_6") (pintype "passive"))
      (node (ref "SEN2-S") (pin "6") (pinfunction "6_6") (pintype "passive"))
      (node (ref "SEN3") (pin "6") (pinfunction "6_6") (pintype "passive"))
      (node (ref "SEN3-S") (pin "6") (pinfunction "6_6") (pintype "passive"))
    )
    (net (code "31") (name "/MISO_M") (class "Default")
      (node (ref "R3") (pin "2") (pinfunction "2_2") (pintype "passive"))
      (node (ref "T2") (pin "14") (pinfunction "14_14") (pintype "passive"))
      (node (ref "T3") (pin "14") (pinfunction "14_14") (pintype "passive"))
      (node (ref "T4") (pin "14") (pinfunction "14_14") (pintype "passive"))
    )
    (net (code "32") (name "/MOSI") (class "Default")
      (node (ref "C19") (pin "2") (pinfunction "2_2") (pintype "passive"))
      (node (ref "R4") (pin "1") (pinfunction "1_1") (pintype "passive"))
      (node (ref "SEN0") (pin "4") (pinfunction "4_4") (pintype "passive"))
      (node (ref "SEN0-S") (pin "4") (pinfunction "4_4") (pintype "passive"))
      (node (ref "SEN1") (pin "4") (pinfunction "4_4") (pintype "passive"))
      (node (ref "SEN1-S") (pin "4") (pinfunction "4_4") (pintype "passive"))
      (node (ref "SEN2") (pin "4") (pinfunction "4_4") (pintype "passive"))
      (node (ref "SEN2-S") (pin "4") (pinfunction "4_4") (pintype "passive"))
      (node (ref "SEN3") (pin "4") (pinfunction "4_4") (pintype "passive"))
      (node (ref "SEN3-S") (pin "4") (pinfunction "4_4") (pintype "passive"))
    )
    (net (code "33") (name "/MOSI1") (class "Default")
      (node (ref "C25") (pin "2") (pinfunction "2_2") (pintype "passive"))
      (node (ref "DISPLAY") (pin "3") (pinfunction "3_3") (pintype "passive"))
      (node (ref "R20") (pin "1") (pinfunction "1_1") (pintype "passive"))
    )
    (net (code "34") (name "/MOSI1_M") (class "Default")
      (node (ref "R20") (pin "2") (pinfunction "2_2") (pintype "passive"))
      (node (ref "T2") (pin "18") (pinfunction "18_18") (pintype "passive"))
      (node (ref "T3") (pin "18") (pinfunction "18_18") (pintype "passive"))
      (node (ref "T4") (pin "18") (pinfunction "18_18") (pintype "passive"))
    )
    (net (code "35") (name "/MOSI_M") (class "Default")
      (node (ref "R4") (pin "2") (pinfunction "2_2") (pintype "passive"))
      (node (ref "T2") (pin "13") (pinfunction "13_13") (pintype "passive"))
      (node (ref "T3") (pin "13") (pinfunction "13_13") (pintype "passive"))
      (node (ref "T4") (pin "13") (pinfunction "13_13") (pintype "passive"))
    )
    (net (code "36") (name "/RST") (class "Default")
      (node (ref "DISPLAY") (pin "7") (pinfunction "7_7") (pintype "passive"))
      (node (ref "T2") (pin "17") (pinfunction "17_17") (pintype "passive"))
      (node (ref "T3") (pin "17") (pinfunction "17_17") (pintype "passive"))
      (node (ref "T4") (pin "17") (pinfunction "17_17") (pintype "passive"))
    )
    (net (code "37") (name "/RX_X") (class "Default")
      (node (ref "HX2") (pin "4") (pinfunction "4_4") (pintype "passive"))
      (node (ref "HY2") (pin "4") (pinfunction "4_4") (pintype "passive"))
      (node (ref "HZ2") (pin "4") (pinfunction "4_4") (pintype "passive"))
      (node (ref "R8") (pin "2") (pinfunction "2_2") (pintype "passive"))
      (node (ref "T1") (pin "14") (pinfunction "14_14") (pintype "passive"))
      (node (ref "T5") (pin "14") (pinfunction "14_14") (pintype "passive"))
      (node (ref "T6") (pin "14") (pinfunction "14_14") (pintype "passive"))
    )
    (net (code "38") (name "/SCK") (class "Default")
      (node (ref "C20") (pin "2") (pinfunction "2_2") (pintype "passive"))
      (node (ref "R5") (pin "1") (pinfunction "1_1") (pintype "passive"))
      (node (ref "SEN0") (pin "2") (pinfunction "2_2") (pintype "passive"))
      (node (ref "SEN0-S") (pin "2") (pinfunction "2_2") (pintype "passive"))
      (node (ref "SEN1") (pin "2") (pinfunction "2_2") (pintype "passive"))
      (node (ref "SEN1-S") (pin "2") (pinfunction "2_2") (pintype "passive"))
      (node (ref "SEN2") (pin "2") (pinfunction "2_2") (pintype "passive"))
      (node (ref "SEN2-S") (pin "2") (pinfunction "2_2") (pintype "passive"))
      (node (ref "SEN3") (pin "2") (pinfunction "2_2") (pintype "passive"))
      (node (ref "SEN3-S") (pin "2") (pinfunction "2_2") (pintype "passive"))
    )
    (net (code "39") (name "/SCK1") (class "Default")
      (node (ref "C26") (pin "2") (pinfunction "2_2") (pintype "passive"))
      (node (ref "DISPLAY") (pin "4") (pinfunction "4_4") (pintype "passive"))
      (node (ref "R21") (pin "1") (pinfunction "1_1") (pintype "passive"))
    )
    (net (code "40") (name "/SCK1_M") (class "Default")
      (node (ref "R21") (pin "2") (pinfunction "2_2") (pintype "passive"))
      (node (ref "T2") (pin "19") (pinfunction "19_19") (pintype "passive"))
      (node (ref "T3") (pin "19") (pinfunction "19_19") (pintype "passive"))
      (node (ref "T4") (pin "19") (pinfunction "19_19") (pintype "passive"))
    )
    (net (code "41") (name "/SCK_M") (class "Default")
      (node (ref "R5") (pin "2") (pinfunction "2_2") (pintype "passive"))
      (node (ref "T1") (pin "11") (pinfunction "11_11") (pintype "passive"))
      (node (ref "T5") (pin "11") (pinfunction "11_11") (pintype "passive"))
      (node (ref "T6") (pin "11") (pinfunction "11_11") (pintype "passive"))
    )
    (net (code "42") (name "/STP_X") (class "Default")
      (node (ref "HX2") (pin "7") (pinfunction "7_7") (pintype "passive"))
      (node (ref "T1") (pin "17") (pinfunction "17_17") (pintype "passive"))
      (node (ref "T5") (pin "17") (pinfunction "17_17") (pintype "passive"))
      (node (ref "T6") (pin "17") (pinfunction "17_17") (pintype "passive"))
    )
    (net (code "43") (name "/STP_Y") (class "Default")
      (node (ref "HY2") (pin "7") (pinfunction "7_7") (pintype "passive"))
      (node (ref "T1") (pin "7") (pinfunction "7_7") (pintype "passive"))
      (node (ref "T5") (pin "7") (pinfunction "7_7") (pintype "passive"))
      (node (ref "T6") (pin "7") (pinfunction "7_7") (pintype "passive"))
    )
    (net (code "44") (name "/STP_Z") (class "Default")
      (node (ref "HZ2") (pin "7") (pinfunction "7_7") (pintype "passive"))
      (node (ref "T1") (pin "1") (pinfunction "1_1") (pintype "passive"))
      (node (ref "T5") (pin "1") (pinfunction "1_1") (pintype "passive"))
      (node (ref "T6") (pin "1") (pinfunction "1_1") (pintype "passive"))
    )
    (net (code "45") (name "GND") (class "Default")
      (node (ref "24V_IN") (pin "1") (pinfunction "1_1") (pintype "passive"))
      (node (ref "5V_IN") (pin "1") (pinfunction "1_1") (pintype "passive"))
      (node (ref "C1") (pin "-") (pinfunction "-_-") (pintype "passive"))
      (node (ref "C10") (pin "2") (pinfunction "2_2") (pintype "passive"))
      (node (ref "C11") (pin "2") (pinfunction "2_2") (pintype "passive"))
      (node (ref "C12") (pin "-") (pinfunction "-_-") (pintype "passive"))
      (node (ref "C13") (pin "-") (pinfunction "-_-") (pintype "passive"))
      (node (ref "C14") (pin "2") (pinfunction "2_2") (pintype "passive"))
      (node (ref "C15") (pin "2") (pinfunction "2_2") (pintype "passive"))
      (node (ref "C16") (pin "2") (pinfunction "2_2") (pintype "passive"))
      (node (ref "C17") (pin "2") (pinfunction "2_2") (pintype "passive"))
      (node (ref "C18") (pin "1") (pinfunction "1_1") (pintype "passive"))
      (node (ref "C19") (pin "1") (pinfunction "1_1") (pintype "passive"))
      (node (ref "C2") (pin "-") (pinfunction "-_-") (pintype "passive"))
      (node (ref "C20") (pin "1") (pinfunction "1_1") (pintype "passive"))
      (node (ref "C21") (pin "1") (pinfunction "1_1") (pintype "passive"))
      (node (ref "C22") (pin "1") (pinfunction "1_1") (pintype "passive"))
      (node (ref "C23") (pin "1") (pinfunction "1_1") (pintype "passive"))
      (node (ref "C24") (pin "1") (pinfunction "1_1") (pintype "passive"))
      (node (ref "C25") (pin "1") (pinfunction "1_1") (pintype "passive"))
      (node (ref "C26") (pin "1") (pinfunction "1_1") (pintype "passive"))
      (node (ref "C27") (pin "1") (pinfunction "1_1") (pintype "passive"))
      (node (ref "C28") (pin "2") (pinfunction "2_2") (pintype "passive"))
      (node (ref "C3") (pin "2") (pinfunction "2_2") (pintype "passive"))
      (node (ref "C4") (pin "2") (pinfunction "2_2") (pintype "passive"))
      (node (ref "C5") (pin "2") (pinfunction "2_2") (pintype "passive"))
      (node (ref "C6") (pin "2") (pinfunction "2_2") (pintype "passive"))
      (node (ref "C7") (pin "2") (pinfunction "2_2") (pintype "passive"))
      (node (ref "C8") (pin "2") (pinfunction "2_2") (pintype "passive"))
      (node (ref "CR1") (pin "2") (pinfunction "2_2") (pintype "passive"))
      (node (ref "DISPLAY") (pin "2") (pinfunction "2_2") (pintype "passive"))
      (node (ref "G1") (pin "1") (pinfunction "1_1") (pintype "passive"))
      (node (ref "G1") (pin "2") (pinfunction "2_2") (pintype "passive"))
      (node (ref "G1") (pin "3") (pinfunction "3_3") (pintype "passive"))
      (node (ref "HX1") (pin "1") (pinfunction "1_1") (pintype "passive"))
      (node (ref "HX1") (pin "7") (pinfunction "7_7") (pintype "passive"))
      (node (ref "HX2") (pin "2") (pinfunction "2_2") (pintype "passive"))
      (node (ref "HX2") (pin "3") (pinfunction "3_3") (pintype "passive"))
      (node (ref "HY1") (pin "1") (pinfunction "1_1") (pintype "passive"))
      (node (ref "HY1") (pin "7") (pinfunction "7_7") (pintype "passive"))
      (node (ref "HY2") (pin "3") (pinfunction "3_3") (pintype "passive"))
      (node (ref "HZ1") (pin "1") (pinfunction "1_1") (pintype "passive"))
      (node (ref "HZ1") (pin "7") (pinfunction "7_7") (pintype "passive"))
      (node (ref "HZ2") (pin "2") (pinfunction "2_2") (pintype "passive"))
      (node (ref "J5") (pin "10") (pinfunction "10_10") (pintype "passive"))
      (node (ref "J5") (pin "2") (pinfunction "2_2") (pintype "passive"))
      (node (ref "J5") (pin "4") (pinfunction "4_4") (pintype "passive"))
      (node (ref "J5") (pin "6") (pinfunction "6_6") (pintype "passive"))
      (node (ref "J5") (pin "8") (pinfunction "8_8") (pintype "passive"))
      (node (ref "R23") (pin "1") (pinfunction "1_1") (pintype "passive"))
      (node (ref "R25") (pin "1") (pinfunction "1_1") (pintype "passive"))
      (node (ref "S1") (pin "C") (pinfunction "C_C") (pintype "bidirectional"))
      (node (ref "S1") (pin "SW-") (pinfunction "SW-_SW-") (pintype "bidirectional"))
      (node (ref "SEN0") (pin "3") (pinfunction "3_3") (pintype "passive"))
      (node (ref "SEN0") (pin "5") (pinfunction "5_5") (pintype "passive"))
      (node (ref "SEN0") (pin "7") (pinfunction "7_7") (pintype "passive"))
      (node (ref "SEN0") (pin "P1") (pinfunction "SHIELD_P1") (pintype "passive"))
      (node (ref "SEN0") (pin "P2") (pinfunction "SHIELD_P2") (pintype "passive"))
      (node (ref "SEN0-S") (pin "3") (pinfunction "3_3") (pintype "passive"))
      (node (ref "SEN0-S") (pin "5") (pinfunction "5_5") (pintype "passive"))
      (node (ref "SEN0-S") (pin "7") (pinfunction "7_7") (pintype "passive"))
      (node (ref "SEN1") (pin "3") (pinfunction "3_3") (pintype "passive"))
      (node (ref "SEN1") (pin "5") (pinfunction "5_5") (pintype "passive"))
      (node (ref "SEN1") (pin "7") (pinfunction "7_7") (pintype "passive"))
      (node (ref "SEN1") (pin "P1") (pinfunction "SHIELD_P1") (pintype "passive"))
      (node (ref "SEN1") (pin "P2") (pinfunction "SHIELD_P2") (pintype "passive"))
      (node (ref "SEN1-S") (pin "3") (pinfunction "3_3") (pintype "passive"))
      (node (ref "SEN1-S") (pin "5") (pinfunction "5_5") (pintype "passive"))
      (node (ref "SEN1-S") (pin "7") (pinfunction "7_7") (pintype "passive"))
      (node (ref "SEN2") (pin "3") (pinfunction "3_3") (pintype "passive"))
      (node (ref "SEN2") (pin "5") (pinfunction "5_5") (pintype "passive"))
      (node (ref "SEN2") (pin "7") (pinfunction "7_7") (pintype "passive"))
      (node (ref "SEN2") (pin "P1") (pinfunction "SHIELD_P1") (pintype "passive"))
      (node (ref "SEN2") (pin "P2") (pinfunction "SHIELD_P2") (pintype "passive"))
      (node (ref "SEN2-S") (pin "3") (pinfunction "3_3") (pintype "passive"))
      (node (ref "SEN2-S") (pin "5") (pinfunction "5_5") (pintype "passive"))
      (node (ref "SEN2-S") (pin "7") (pinfunction "7_7") (pintype "passive"))
      (node (ref "SEN3") (pin "3") (pinfunction "3_3") (pintype "passive"))
      (node (ref "SEN3") (pin "5") (pinfunction "5_5") (pintype "passive"))
      (node (ref "SEN3") (pin "7") (pinfunction "7_7") (pintype "passive"))
      (node (ref "SEN3") (pin "P1") (pinfunction "SHIELD_P1") (pintype "passive"))
      (node (ref "SEN3") (pin "P2") (pinfunction "SHIELD_P2") (pintype "passive"))
      (node (ref "SEN3-S") (pin "3") (pinfunction "3_3") (pintype "passive"))
      (node (ref "SEN3-S") (pin "5") (pinfunction "5_5") (pintype "passive"))
      (node (ref "SEN3-S") (pin "7") (pinfunction "7_7") (pintype "passive"))
      (node (ref "T1") (pin "10") (pinfunction "10_10") (pintype "passive"))
      (node (ref "T1") (pin "23") (pinfunction "23_23") (pintype "passive"))
      (node (ref "T2") (pin "1") (pinfunction "1_1") (pintype "passive"))
      (node (ref "T3") (pin "1") (pinfunction "1_1") (pintype "passive"))
      (node (ref "T4") (pin "1") (pinfunction "1_1") (pintype "passive"))
      (node (ref "T5") (pin "10") (pinfunction "10_10") (pintype "passive"))
      (node (ref "T5") (pin "23") (pinfunction "23_23") (pintype "passive"))
      (node (ref "T6") (pin "10") (pinfunction "10_10") (pintype "passive"))
      (node (ref "T6") (pin "23") (pinfunction "23_23") (pintype "passive"))
      (node (ref "U1") (pin "7") (pinfunction "GND_7") (pintype "power_in"))
      (node (ref "U1") (pin "EPAD") (pinfunction "EPAD_EPAD") (pintype "passive"))
    )
    (net (code "46") (name "Net-(C7-Pad1)") (class "Default")
      (node (ref "C7") (pin "1") (pinfunction "1_1") (pintype "passive"))
      (node (ref "R24") (pin "1") (pinfunction "1_1") (pintype "passive"))
    )
    (net (code "47") (name "Net-(HX1-Pad3)") (class "Default")
      (node (ref "HX1") (pin "3") (pinfunction "3_3") (pintype "passive"))
      (node (ref "X_OUT") (pin "1") (pinfunction "1_1") (pintype "bidirectional"))
    )
    (net (code "48") (name "Net-(HX1-Pad4)") (class "Default")
      (node (ref "HX1") (pin "4") (pinfunction "4_4") (pintype "passive"))
      (node (ref "X_OUT") (pin "2") (pinfunction "2_2") (pintype "bidirectional"))
    )
    (net (code "49") (name "Net-(HX1-Pad5)") (class "Default")
      (node (ref "HX1") (pin "5") (pinfunction "5_5") (pintype "passive"))
      (node (ref "X_OUT") (pin "3") (pinfunction "3_3") (pintype "bidirectional"))
    )
    (net (code "50") (name "Net-(HX1-Pad6)") (class "Default")
      (node (ref "HX1") (pin "6") (pinfunction "6_6") (pintype "passive"))
      (node (ref "X_OUT") (pin "4") (pinfunction "4_4") (pintype "bidirectional"))
    )
    (net (code "51") (name "Net-(HY1-Pad3)") (class "Default")
      (node (ref "HY1") (pin "3") (pinfunction "3_3") (pintype "passive"))
      (node (ref "Y_OUT") (pin "1") (pinfunction "1_1") (pintype "bidirectional"))
    )
    (net (code "52") (name "Net-(HY1-Pad4)") (class "Default")
      (node (ref "HY1") (pin "4") (pinfunction "4_4") (pintype "passive"))
      (node (ref "Y_OUT") (pin "2") (pinfunction "2_2") (pintype "bidirectional"))
    )
    (net (code "53") (name "Net-(HY1-Pad5)") (class "Default")
      (node (ref "HY1") (pin "5") (pinfunction "5_5") (pintype "passive"))
      (node (ref "Y_OUT") (pin "3") (pinfunction "3_3") (pintype "bidirectional"))
    )
    (net (code "54") (name "Net-(HY1-Pad6)") (class "Default")
      (node (ref "HY1") (pin "6") (pinfunction "6_6") (pintype "passive"))
      (node (ref "Y_OUT") (pin "4") (pinfunction "4_4") (pintype "bidirectional"))
    )
    (net (code "55") (name "Net-(HZ1-Pad3)") (class "Default")
      (node (ref "HZ1") (pin "3") (pinfunction "3_3") (pintype "passive"))
      (node (ref "Z_OUT") (pin "1") (pinfunction "1_1") (pintype "bidirectional"))
    )
    (net (code "56") (name "Net-(HZ1-Pad4)") (class "Default")
      (node (ref "HZ1") (pin "4") (pinfunction "4_4") (pintype "passive"))
      (node (ref "Z_OUT") (pin "2") (pinfunction "2_2") (pintype "bidirectional"))
    )
    (net (code "57") (name "Net-(HZ1-Pad5)") (class "Default")
      (node (ref "HZ1") (pin "5") (pinfunction "5_5") (pintype "passive"))
      (node (ref "Z_OUT") (pin "3") (pinfunction "3_3") (pintype "bidirectional"))
    )
    (net (code "58") (name "Net-(HZ1-Pad6)") (class "Default")
      (node (ref "HZ1") (pin "6") (pinfunction "6_6") (pintype "passive"))
      (node (ref "Z_OUT") (pin "4") (pinfunction "4_4") (pintype "bidirectional"))
    )
    (net (code "59") (name "Net-(R8-Pad1)") (class "Default")
      (node (ref "R8") (pin "1") (pinfunction "1_1") (pintype "passive"))
      (node (ref "T1") (pin "15") (pinfunction "15_15") (pintype "passive"))
      (node (ref "T5") (pin "15") (pinfunction "15_15") (pintype "passive"))
      (node (ref "T6") (pin "15") (pinfunction "15_15") (pintype "passive"))
    )
    (net (code "60") (name "Net-(T1-Pad2)") (class "Default")
      (node (ref "T1") (pin "2") (pinfunction "2_2") (pintype "passive"))
      (node (ref "T5") (pin "2") (pinfunction "2_2") (pintype "passive"))
      (node (ref "T6") (pin "2") (pinfunction "2_2") (pintype "passive"))
    )
    (net (code "61") (name "Net-(T1-Pad3)") (class "Default")
      (node (ref "T1") (pin "3") (pinfunction "3_3") (pintype "passive"))
      (node (ref "T5") (pin "3") (pinfunction "3_3") (pintype "passive"))
      (node (ref "T6") (pin "3") (pinfunction "3_3") (pintype "passive"))
    )
    (net (code "62") (name "Net-(T1-Pad5)") (class "Default")
      (node (ref "T1") (pin "5") (pinfunction "5_5") (pintype "passive"))
      (node (ref "T5") (pin "5") (pinfunction "5_5") (pintype "passive"))
      (node (ref "T6") (pin "5") (pinfunction "5_5") (pintype "passive"))
    )
    (net (code "63") (name "Net-(T1-Pad8)") (class "Default")
      (node (ref "T1") (pin "8") (pinfunction "8_8") (pintype "passive"))
      (node (ref "T5") (pin "8") (pinfunction "8_8") (pintype "passive"))
      (node (ref "T6") (pin "8") (pinfunction "8_8") (pintype "passive"))
    )
    (net (code "64") (name "Net-(T1-Pad12)") (class "Default")
      (node (ref "T1") (pin "12") (pinfunction "12_12") (pintype "passive"))
      (node (ref "T5") (pin "12") (pinfunction "12_12") (pintype "passive"))
      (node (ref "T6") (pin "12") (pinfunction "12_12") (pintype "passive"))
    )
    (net (code "65") (name "Net-(T1-Pad18)") (class "Default")
      (node (ref "T1") (pin "18") (pinfunction "18_18") (pintype "passive"))
      (node (ref "T5") (pin "18") (pinfunction "18_18") (pintype "passive"))
      (node (ref "T6") (pin "18") (pinfunction "18_18") (pintype "passive"))
    )
    (net (code "66") (name "Net-(T2-Pad2)") (class "Default")
      (node (ref "T2") (pin "2") (pinfunction "2_2") (pintype "passive"))
      (node (ref "T3") (pin "2") (pinfunction "2_2") (pintype "passive"))
      (node (ref "T4") (pin "2") (pinfunction "2_2") (pintype "passive"))
    )
    (net (code "67") (name "Net-(T2-Pad3)") (class "Default")
      (node (ref "T2") (pin "3") (pinfunction "3_3") (pintype "passive"))
      (node (ref "T3") (pin "3") (pinfunction "3_3") (pintype "passive"))
      (node (ref "T4") (pin "3") (pinfunction "3_3") (pintype "passive"))
    )
    (net (code "68") (name "Net-(T2-Pad10)") (class "Default")
      (node (ref "T2") (pin "10") (pinfunction "10_10") (pintype "passive"))
      (node (ref "T3") (pin "10") (pinfunction "10_10") (pintype "passive"))
      (node (ref "T4") (pin "10") (pinfunction "10_10") (pintype "passive"))
    )
    (net (code "69") (name "Net-(T2-Pad11)") (class "Default")
      (node (ref "T2") (pin "11") (pinfunction "11_11") (pintype "passive"))
      (node (ref "T3") (pin "11") (pinfunction "11_11") (pintype "passive"))
      (node (ref "T4") (pin "11") (pinfunction "11_11") (pintype "passive"))
    )
    (net (code "70") (name "Net-(U1-BOOT)") (class "Default")
      (node (ref "C9") (pin "1") (pinfunction "1_1") (pintype "passive"))
      (node (ref "U1") (pin "1") (pinfunction "BOOT_1") (pintype "output"))
    )
    (net (code "71") (name "Net-(U1-COMP)") (class "Default")
      (node (ref "C8") (pin "1") (pinfunction "1_1") (pintype "passive"))
      (node (ref "R24") (pin "2") (pinfunction "2_2") (pintype "passive"))
      (node (ref "U1") (pin "6") (pinfunction "COMP_6") (pintype "output"))
    )
    (net (code "72") (name "Net-(U1-FB)") (class "Default")
      (node (ref "R25") (pin "2") (pinfunction "2_2") (pintype "passive"))
      (node (ref "R26") (pin "1") (pinfunction "1_1") (pintype "passive"))
      (node (ref "U1") (pin "5") (pinfunction "FB_5") (pintype "input"))
    )
    (net (code "73") (name "Net-(U1-RT{slash}CLK)") (class "Default")
      (node (ref "R23") (pin "2") (pinfunction "2_2") (pintype "passive"))
      (node (ref "U1") (pin "4") (pinfunction "RT/CLK_4") (pintype "input"))
    )
    (net (code "74") (name "Net-(U1-SW)") (class "Default")
      (node (ref "C9") (pin "2") (pinfunction "2_2") (pintype "passive"))
      (node (ref "CR1") (pin "1") (pinfunction "1_1") (pintype "passive"))
      (node (ref "L1") (pin "1") (pinfunction "1_1") (pintype "passive"))
      (node (ref "U1") (pin "8") (pinfunction "SW_8") (pintype "input"))
    )
    (net (code "75") (name "unconnected-(HX2-Pad5)") (class "Default")
      (node (ref "HX2") (pin "5") (pinfunction "5_5") (pintype "passive"))
    )
    (net (code "76") (name "unconnected-(HX2-Pad6)") (class "Default")
      (node (ref "HX2") (pin "6") (pinfunction "6_6") (pintype "passive"))
    )
    (net (code "77") (name "unconnected-(HY2-Pad5)") (class "Default")
      (node (ref "HY2") (pin "5") (pinfunction "5_5") (pintype "passive"))
    )
    (net (code "78") (name "unconnected-(HY2-Pad6)") (class "Default")
      (node (ref "HY2") (pin "6") (pinfunction "6_6") (pintype "passive"))
    )
    (net (code "79") (name "unconnected-(HZ2-Pad5)") (class "Default")
      (node (ref "HZ2") (pin "5") (pinfunction "5_5") (pintype "passive"))
    )
    (net (code "80") (name "unconnected-(HZ2-Pad6)") (class "Default")
      (node (ref "HZ2") (pin "6") (pinfunction "6_6") (pintype "passive"))
    )
    (net (code "81") (name "unconnected-(U1-EN-Pad3)") (class "Default")
      (node (ref "U1") (pin "3") (pinfunction "EN_3") (pintype "input"))
    )
  )
)
